# pCog105_LogicStart.net
KiCad netlist of a schematic drawn in EAGLE
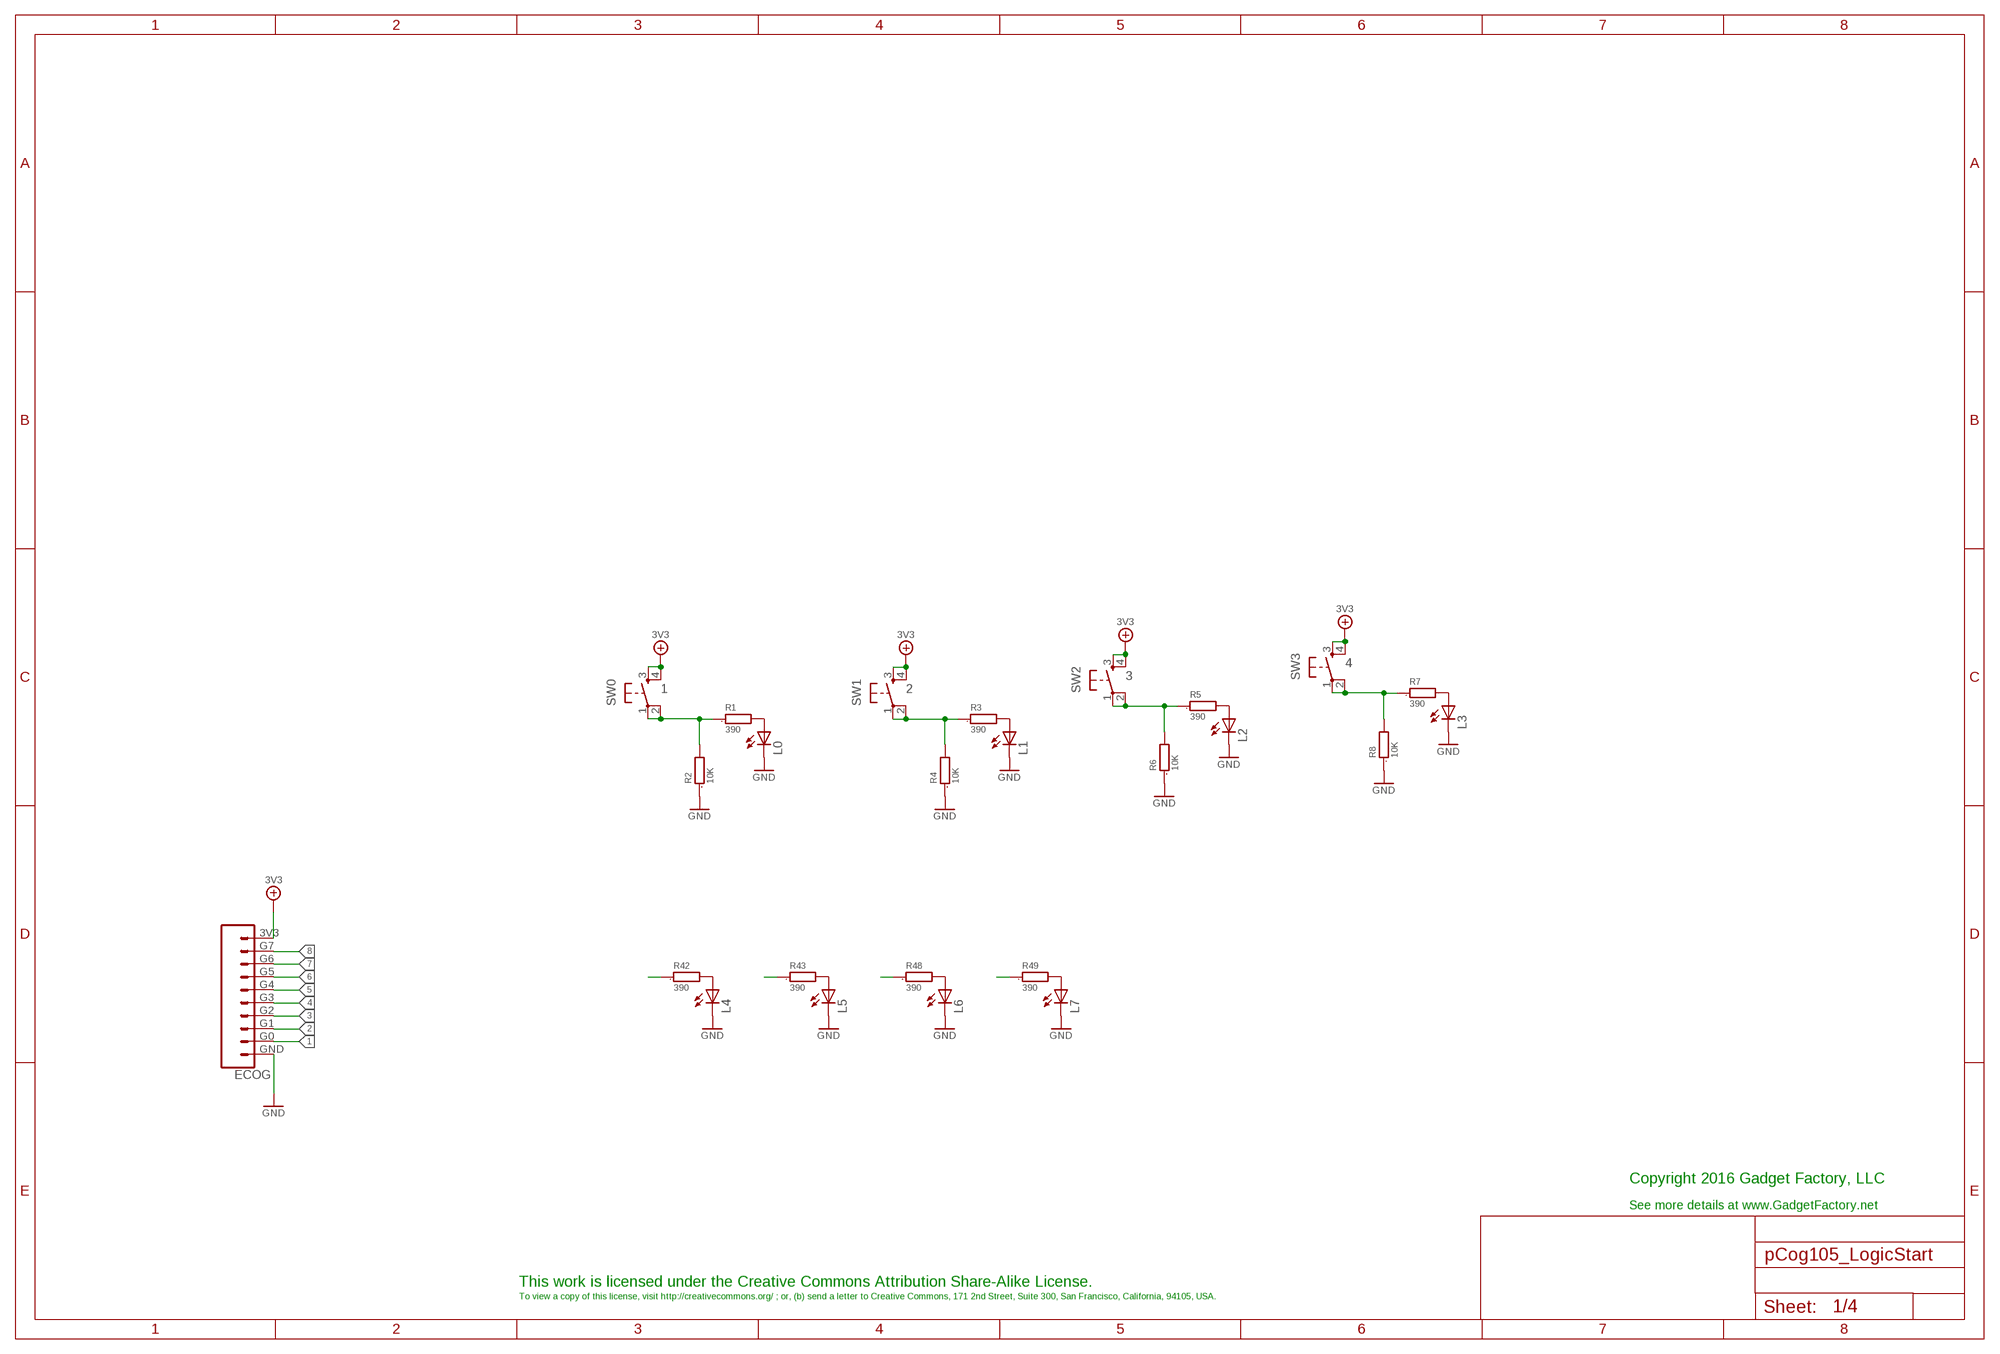
[diagram p0: schematic, sheet 1]
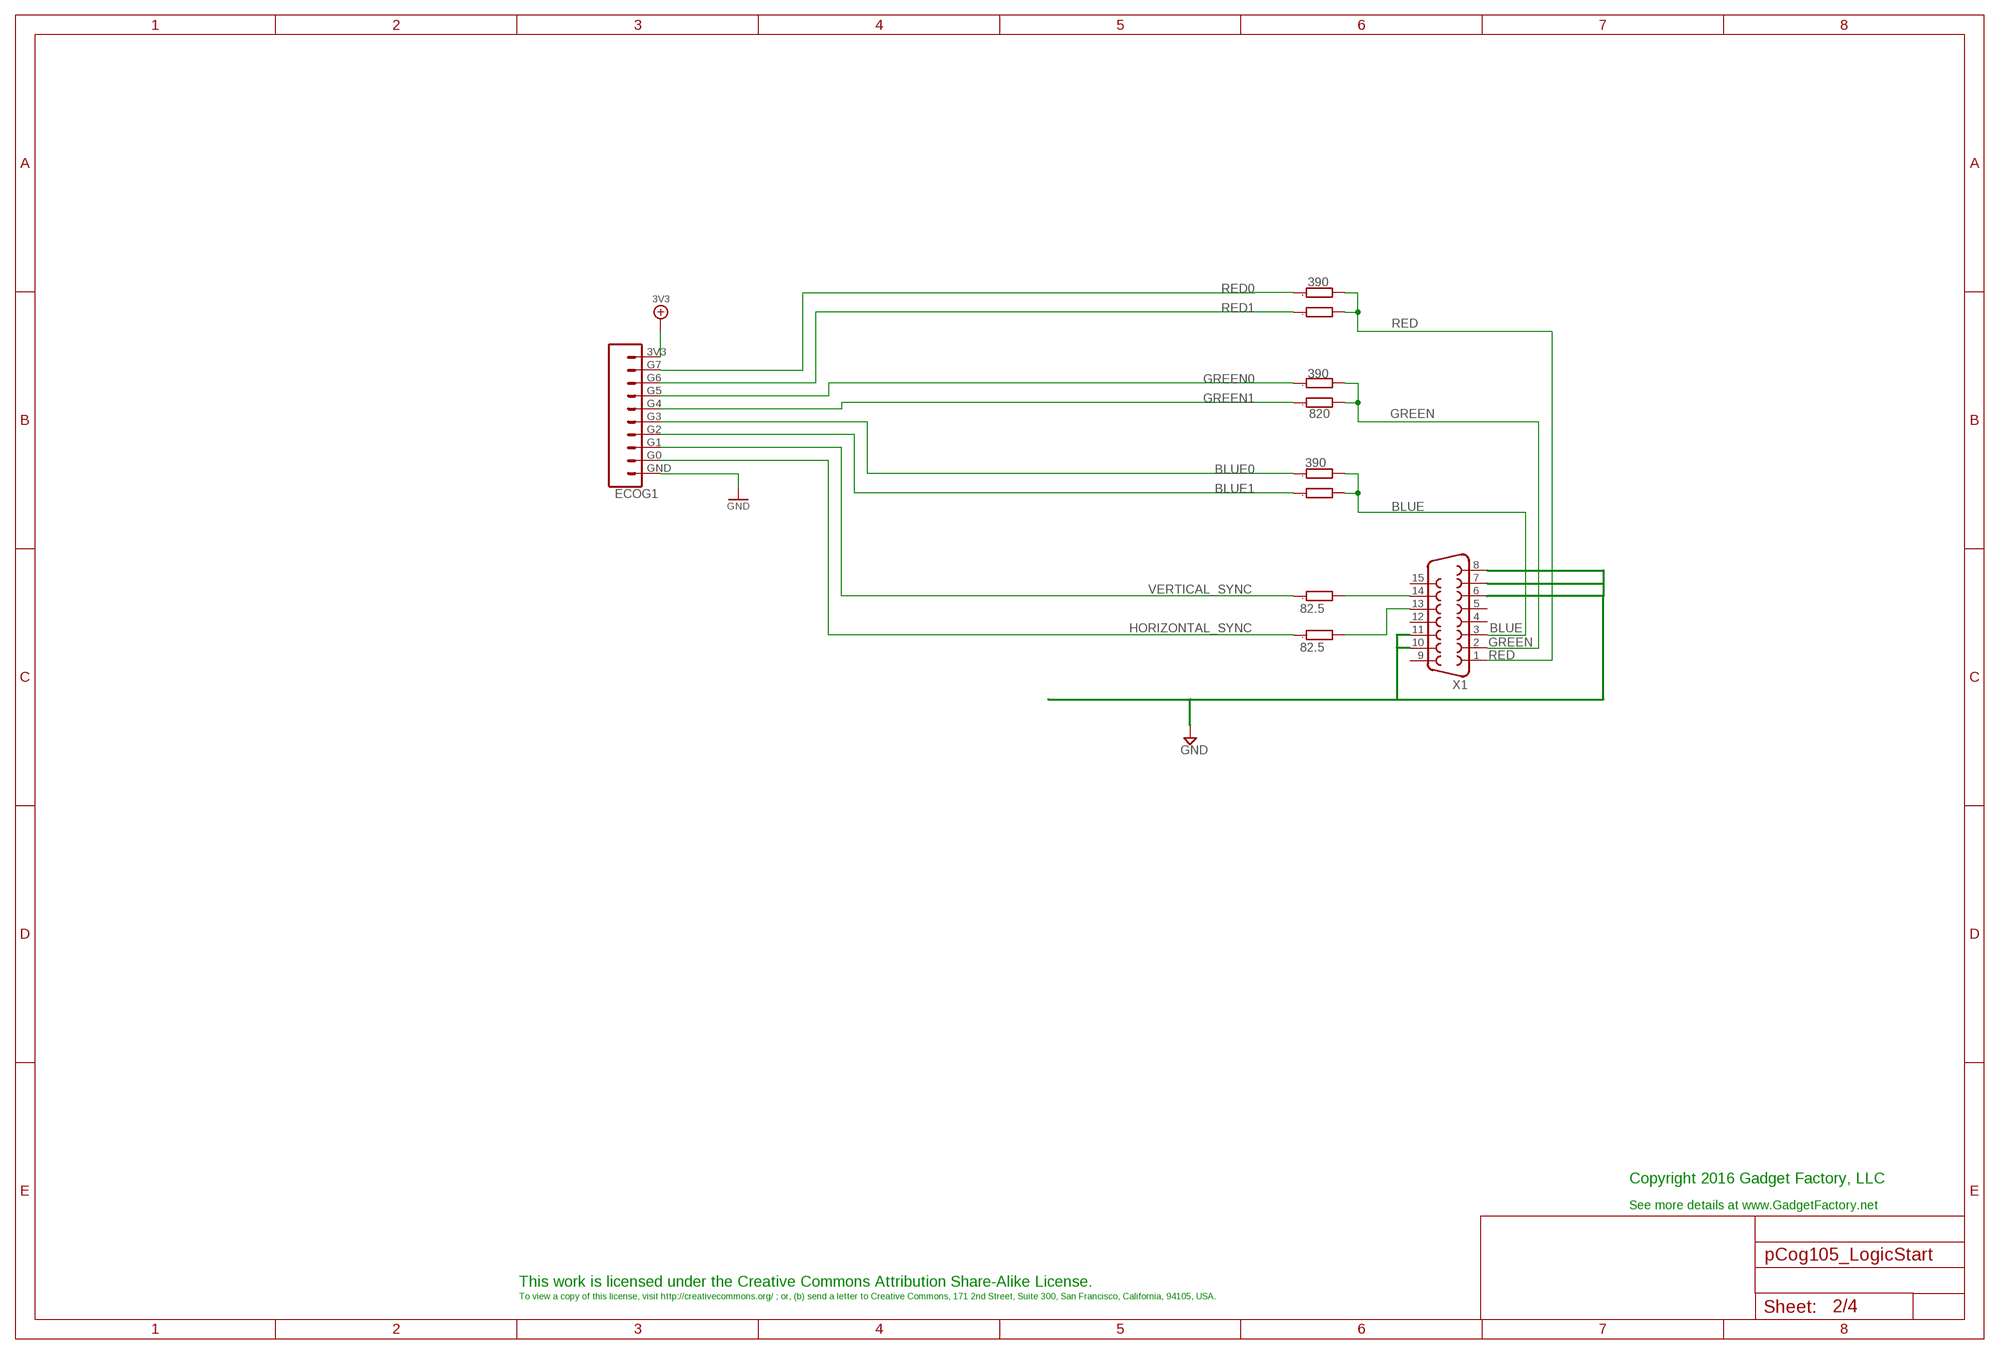
[diagram p1: schematic, sheet 2]
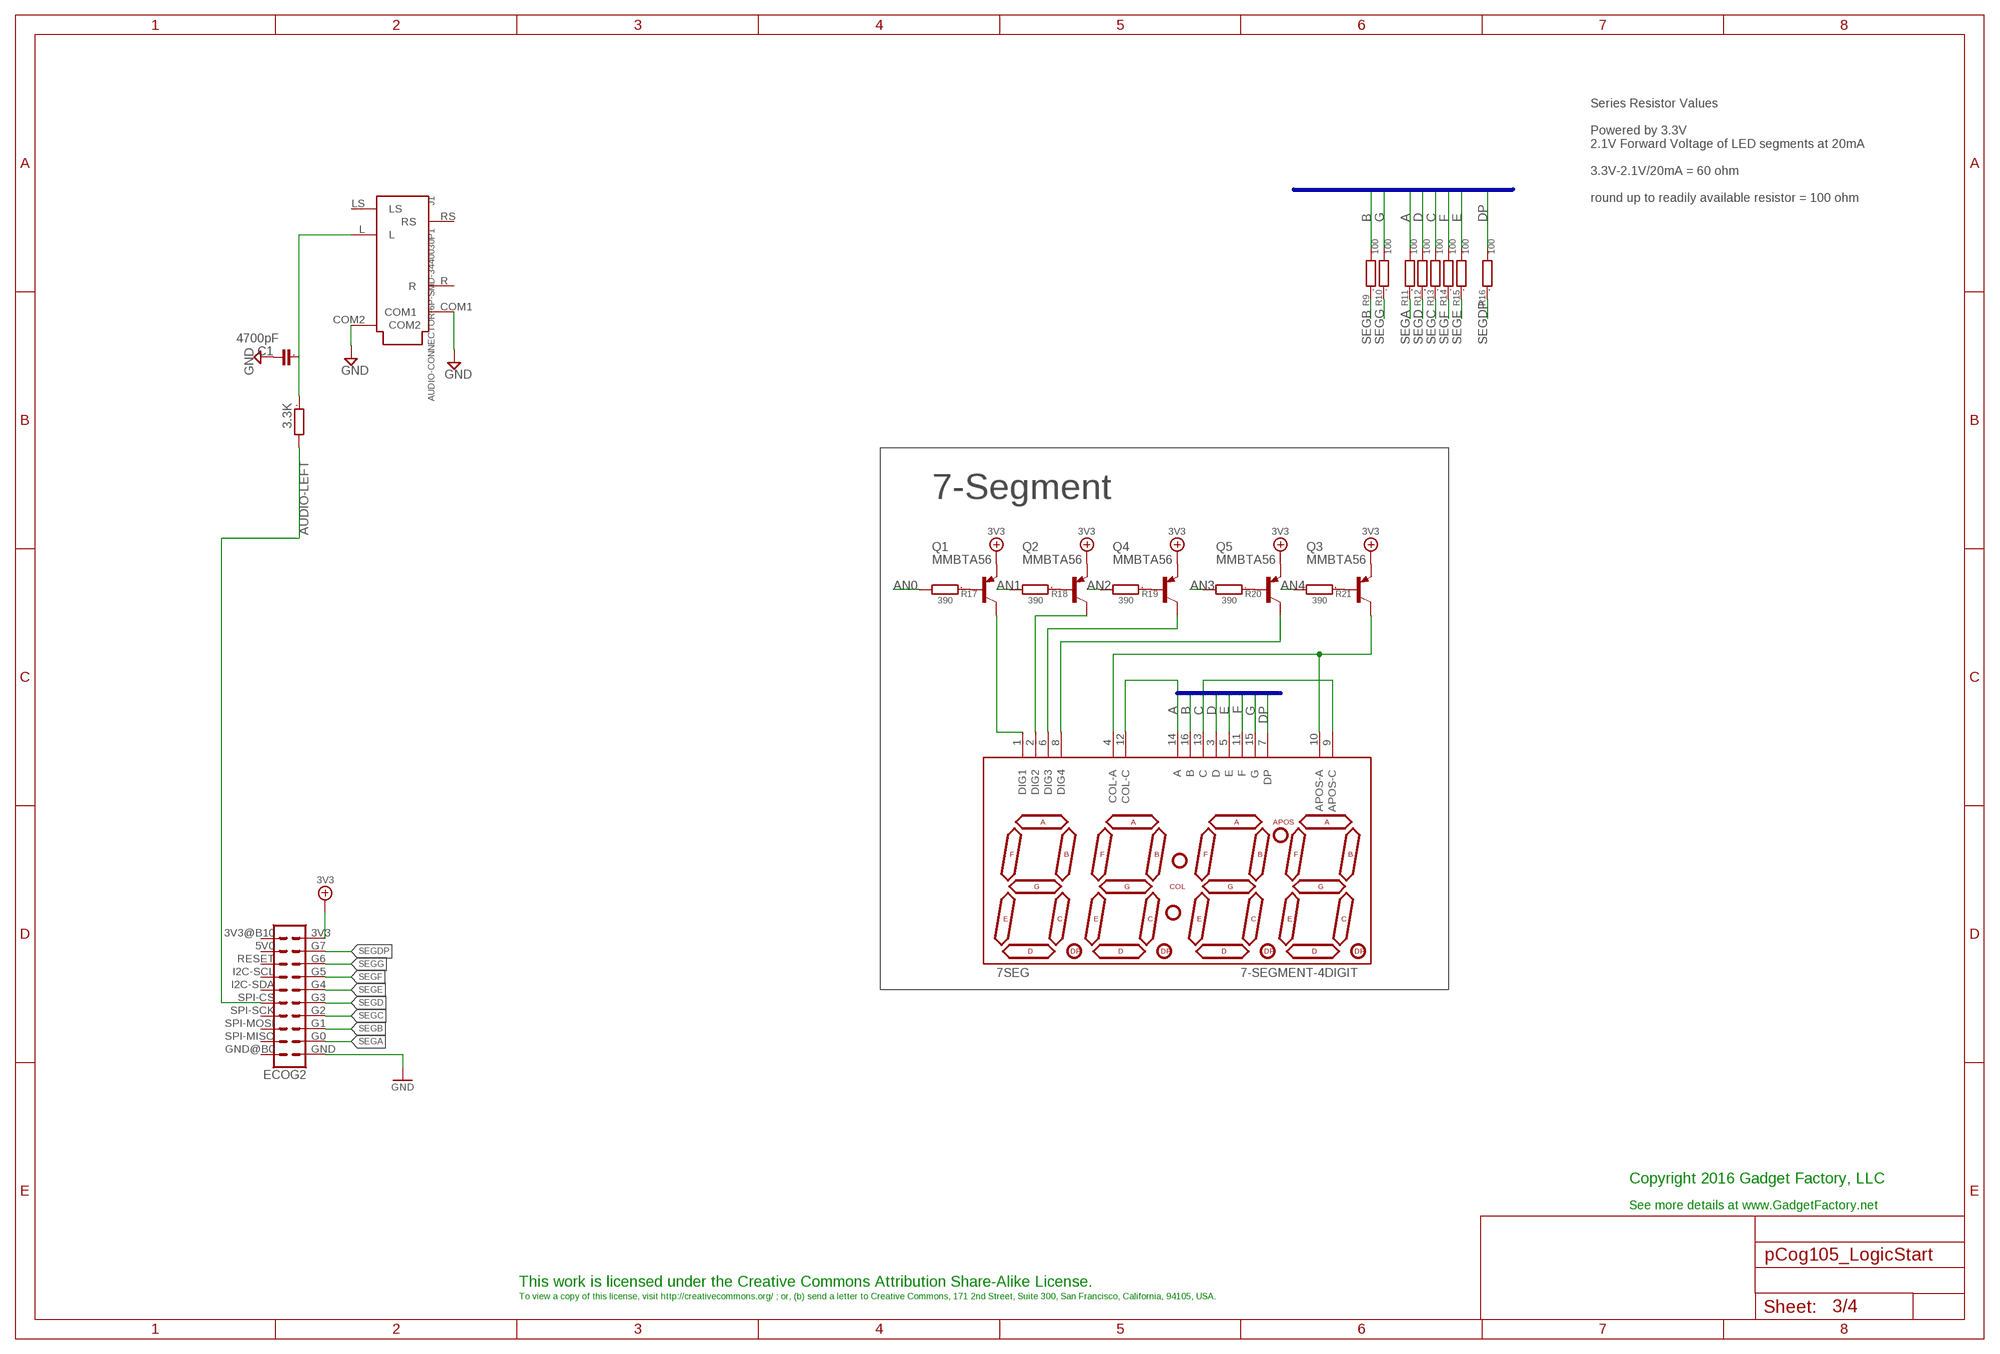
[diagram p2: schematic, sheet 3]
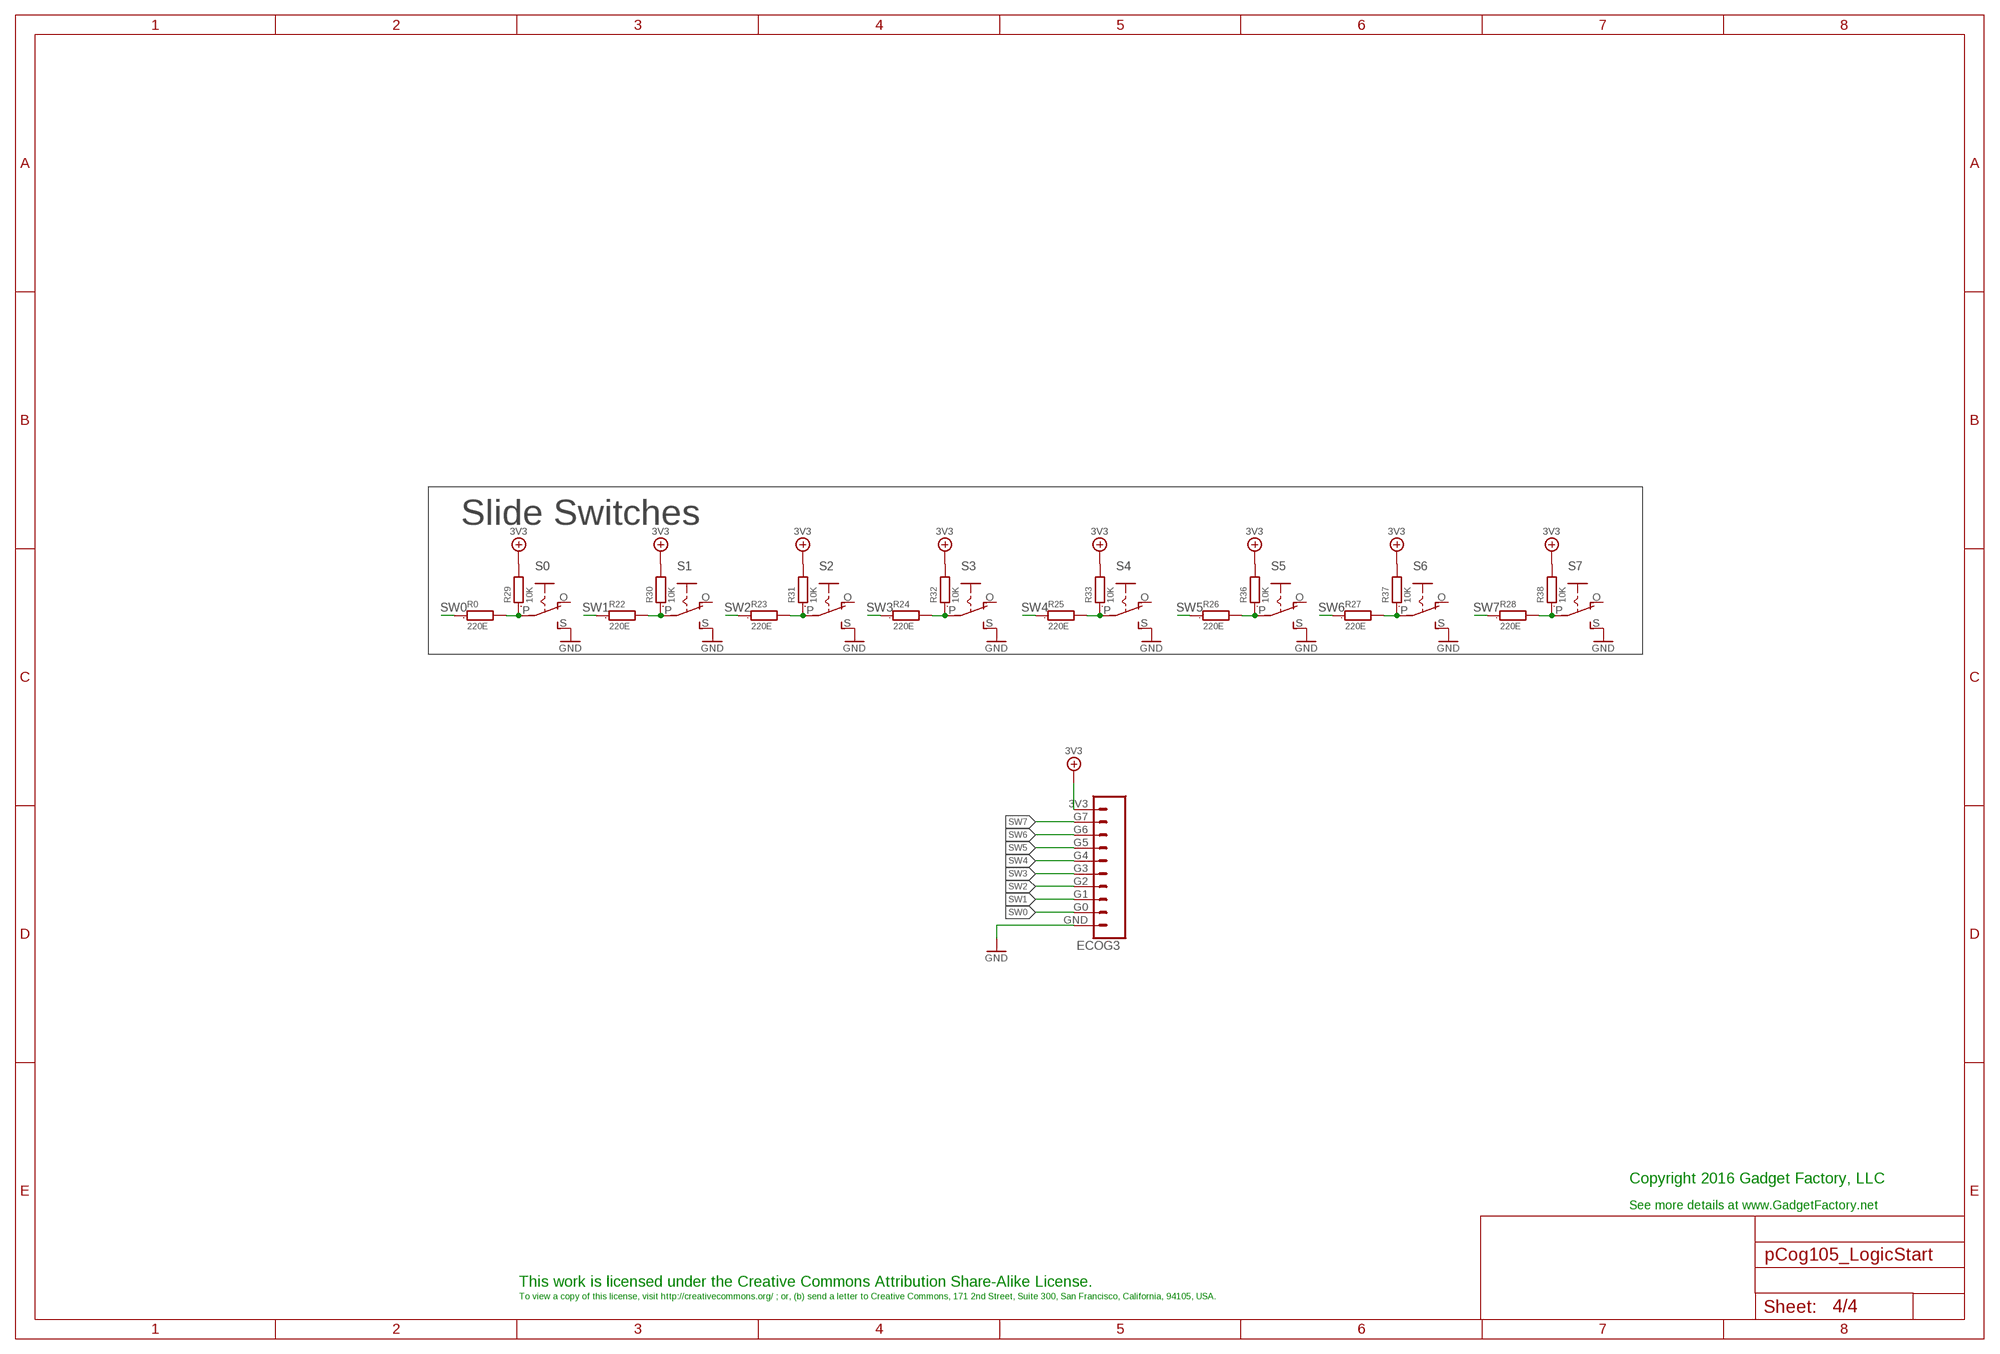
[diagram p3: schematic, sheet 4]

(export (version "E")
  (design (tool "Eeschema 10.0.6"))
  (components
    (comp (ref "ECOG")
      (value "ECOG_GENERAL_ROWTHROUGHOLE")
      (footprint "eagle-import:ECOG_GENERAL_TH")
      (libsource (lib "eagle-import") (part "ECOG_GENERAL_ROWTHROUGHOLE"))
    )
    (comp (ref "L0")
      (value "LEDCHIP-LED0805")
      (footprint "eagle-import:CHIP-LED0805")
      (libsource (lib "eagle-import") (part "LEDCHIP-LED0805"))
    )
    (comp (ref "L1")
      (value "LEDCHIP-LED0805")
      (footprint "eagle-import:CHIP-LED0805")
      (libsource (lib "eagle-import") (part "LEDCHIP-LED0805"))
    )
    (comp (ref "L2")
      (value "LEDCHIP-LED0805")
      (footprint "eagle-import:CHIP-LED0805")
      (libsource (lib "eagle-import") (part "LEDCHIP-LED0805"))
    )
    (comp (ref "L3")
      (value "LEDCHIP-LED0805")
      (footprint "eagle-import:CHIP-LED0805")
      (libsource (lib "eagle-import") (part "LEDCHIP-LED0805"))
    )
    (comp (ref "L4")
      (value "LEDCHIP-LED0805")
      (footprint "eagle-import:CHIP-LED0805")
      (libsource (lib "eagle-import") (part "LEDCHIP-LED0805"))
    )
    (comp (ref "L5")
      (value "LEDCHIP-LED0805")
      (footprint "eagle-import:CHIP-LED0805")
      (libsource (lib "eagle-import") (part "LEDCHIP-LED0805"))
    )
    (comp (ref "L6")
      (value "LEDCHIP-LED0805")
      (footprint "eagle-import:CHIP-LED0805")
      (libsource (lib "eagle-import") (part "LEDCHIP-LED0805"))
    )
    (comp (ref "L7")
      (value "LEDCHIP-LED0805")
      (footprint "eagle-import:CHIP-LED0805")
      (libsource (lib "eagle-import") (part "LEDCHIP-LED0805"))
    )
    (comp (ref "R1")
      (value "390")
      (footprint "eagle-import:0805")
      (libsource (lib "eagle-import") (part "R0805"))
    )
    (comp (ref "R2")
      (value "10K")
      (footprint "eagle-import:0805")
      (libsource (lib "eagle-import") (part "R0805"))
    )
    (comp (ref "R3")
      (value "390")
      (footprint "eagle-import:0805")
      (libsource (lib "eagle-import") (part "R0805"))
    )
    (comp (ref "R4")
      (value "10K")
      (footprint "eagle-import:0805")
      (libsource (lib "eagle-import") (part "R0805"))
    )
    (comp (ref "R5")
      (value "390")
      (footprint "eagle-import:0805")
      (libsource (lib "eagle-import") (part "R0805"))
    )
    (comp (ref "R6")
      (value "10K")
      (footprint "eagle-import:0805")
      (libsource (lib "eagle-import") (part "R0805"))
    )
    (comp (ref "R7")
      (value "390")
      (footprint "eagle-import:0805")
      (libsource (lib "eagle-import") (part "R0805"))
    )
    (comp (ref "R8")
      (value "10K")
      (footprint "eagle-import:0805")
      (libsource (lib "eagle-import") (part "R0805"))
    )
    (comp (ref "R42")
      (value "390")
      (footprint "eagle-import:0805")
      (libsource (lib "eagle-import") (part "R0805"))
    )
    (comp (ref "R43")
      (value "390")
      (footprint "eagle-import:0805")
      (libsource (lib "eagle-import") (part "R0805"))
    )
    (comp (ref "R48")
      (value "390")
      (footprint "eagle-import:0805")
      (libsource (lib "eagle-import") (part "R0805"))
    )
    (comp (ref "R49")
      (value "390")
      (footprint "eagle-import:0805")
      (libsource (lib "eagle-import") (part "R0805"))
    )
    (comp (ref "SW0")
      (value "TAC_SWITCHPTH")
      (footprint "eagle-import:TACTILE-PTH")
      (libsource (lib "eagle-import") (part "TAC_SWITCHPTH"))
    )
    (comp (ref "SW1")
      (value "TAC_SWITCHPTH")
      (footprint "eagle-import:TACTILE-PTH")
      (libsource (lib "eagle-import") (part "TAC_SWITCHPTH"))
    )
    (comp (ref "SW2")
      (value "TAC_SWITCHPTH")
      (footprint "eagle-import:TACTILE-PTH")
      (libsource (lib "eagle-import") (part "TAC_SWITCHPTH"))
    )
    (comp (ref "SW3")
      (value "TAC_SWITCHPTH")
      (footprint "eagle-import:TACTILE-PTH")
      (libsource (lib "eagle-import") (part "TAC_SWITCHPTH"))
    )
    (comp (ref "ECOG1")
      (value "ECOG_GENERAL_ROWTHROUGHOLE")
      (footprint "eagle-import:ECOG_GENERAL_TH")
      (libsource (lib "eagle-import") (part "ECOG_GENERAL_ROWTHROUGHOLE"))
    )
    (comp (ref "R34")
      (value "390")
      (footprint "eagle-import:0603")
      (fields (field (name "PARTNO") "RMCF0603JT3K90"))
      (libsource (lib "eagle-import") (part "R0603"))
    )
    (comp (ref "R35")
      (value "820")
      (footprint "eagle-import:0603")
      (fields (field (name "PARTNO") "RMCF0603JT2K00"))
      (libsource (lib "eagle-import") (part "R0603"))
    )
    (comp (ref "R40")
      (value "820")
      (footprint "eagle-import:0603")
      (fields (field (name "PARTNO") "RMCF0603JT2K00"))
      (libsource (lib "eagle-import") (part "R0603"))
    )
    (comp (ref "R41")
      (value "390")
      (footprint "eagle-import:0603")
      (fields (field (name "PARTNO") "RMCF0603JT3K90"))
      (libsource (lib "eagle-import") (part "R0603"))
    )
    (comp (ref "R44")
      (value "820")
      (footprint "eagle-import:0603")
      (fields (field (name "PARTNO") "RMCF0603JT2K00"))
      (libsource (lib "eagle-import") (part "R0603"))
    )
    (comp (ref "R45")
      (value "390")
      (footprint "eagle-import:0603")
      (fields (field (name "PARTNO") "RMCF0603JT3K90"))
      (libsource (lib "eagle-import") (part "R0603"))
    )
    (comp (ref "R46")
      (value "82.5")
      (footprint "eagle-import:0603")
      (fields (field (name "PARTNO") "RMCF0603FT82R5"))
      (libsource (lib "eagle-import") (part "R0603"))
    )
    (comp (ref "R47")
      (value "82.5")
      (footprint "eagle-import:0603")
      (fields (field (name "PARTNO") "RMCF0603FT82R5"))
      (libsource (lib "eagle-import") (part "R0603"))
    )
    (comp (ref "X1")
      (value "F15HDH")
      (footprint "eagle-import:HDF15H")
      (fields (field (name "PARTNO") "1-1734530-1"))
      (libsource (lib "eagle-import") (part "F15HDH"))
    )
    (comp (ref "ECOG3")
      (value "ECOG_GENERAL_ROWTHROUGHOLE")
      (footprint "eagle-import:ECOG_GENERAL_TH")
      (libsource (lib "eagle-import") (part "ECOG_GENERAL_ROWTHROUGHOLE"))
    )
    (comp (ref "R0")
      (value "220E")
      (footprint "eagle-import:0603")
      (fields (field (name "PARTNO") "RMCF0603JT220R"))
      (libsource (lib "eagle-import") (part "R0603"))
    )
    (comp (ref "R22")
      (value "220E")
      (footprint "eagle-import:0603")
      (fields (field (name "PARTNO") "RMCF0603JT220R"))
      (libsource (lib "eagle-import") (part "R0603"))
    )
    (comp (ref "R23")
      (value "220E")
      (footprint "eagle-import:0603")
      (fields (field (name "PARTNO") "RMCF0603JT220R"))
      (libsource (lib "eagle-import") (part "R0603"))
    )
    (comp (ref "R24")
      (value "220E")
      (footprint "eagle-import:0603")
      (fields (field (name "PARTNO") "RMCF0603JT220R"))
      (libsource (lib "eagle-import") (part "R0603"))
    )
    (comp (ref "R25")
      (value "220E")
      (footprint "eagle-import:0603")
      (fields (field (name "PARTNO") "RMCF0603JT220R"))
      (libsource (lib "eagle-import") (part "R0603"))
    )
    (comp (ref "R26")
      (value "220E")
      (footprint "eagle-import:0603")
      (fields (field (name "PARTNO") "RMCF0603JT220R"))
      (libsource (lib "eagle-import") (part "R0603"))
    )
    (comp (ref "R27")
      (value "220E")
      (footprint "eagle-import:0603")
      (fields (field (name "PARTNO") "RMCF0603JT220R"))
      (libsource (lib "eagle-import") (part "R0603"))
    )
    (comp (ref "R28")
      (value "220E")
      (footprint "eagle-import:0603")
      (fields (field (name "PARTNO") "RMCF0603JT220R"))
      (libsource (lib "eagle-import") (part "R0603"))
    )
    (comp (ref "R29")
      (value "10K")
      (footprint "eagle-import:0603")
      (fields (field (name "PARTNO") "RMCF0603JT10K0"))
      (libsource (lib "eagle-import") (part "R0603"))
    )
    (comp (ref "R30")
      (value "10K")
      (footprint "eagle-import:0603")
      (fields (field (name "PARTNO") "RMCF0603JT10K0"))
      (libsource (lib "eagle-import") (part "R0603"))
    )
    (comp (ref "R31")
      (value "10K")
      (footprint "eagle-import:0603")
      (fields (field (name "PARTNO") "RMCF0603JT10K0"))
      (libsource (lib "eagle-import") (part "R0603"))
    )
    (comp (ref "R32")
      (value "10K")
      (footprint "eagle-import:0603")
      (fields (field (name "PARTNO") "RMCF0603JT10K0"))
      (libsource (lib "eagle-import") (part "R0603"))
    )
    (comp (ref "R33")
      (value "10K")
      (footprint "eagle-import:0603")
      (fields (field (name "PARTNO") "RMCF0603JT10K0"))
      (libsource (lib "eagle-import") (part "R0603"))
    )
    (comp (ref "R36")
      (value "10K")
      (footprint "eagle-import:0603")
      (fields (field (name "PARTNO") "RMCF0603JT10K0"))
      (libsource (lib "eagle-import") (part "R0603"))
    )
    (comp (ref "R37")
      (value "10K")
      (footprint "eagle-import:0603")
      (fields (field (name "PARTNO") "RMCF0603JT10K0"))
      (libsource (lib "eagle-import") (part "R0603"))
    )
    (comp (ref "R38")
      (value "10K")
      (footprint "eagle-import:0603")
      (fields (field (name "PARTNO") "RMCF0603JT10K0"))
      (libsource (lib "eagle-import") (part "R0603"))
    )
    (comp (ref "S0")
      (value "EG1218S")
      (footprint "eagle-import:EG1218")
      (fields (field (name "PARTNO") "EG1218"))
      (libsource (lib "eagle-import") (part "EG1218S"))
    )
    (comp (ref "S1")
      (value "EG1218S")
      (footprint "eagle-import:EG1218")
      (fields (field (name "PARTNO") "EG1218"))
      (libsource (lib "eagle-import") (part "EG1218S"))
    )
    (comp (ref "S2")
      (value "EG1218S")
      (footprint "eagle-import:EG1218")
      (fields (field (name "PARTNO") "EG1218"))
      (libsource (lib "eagle-import") (part "EG1218S"))
    )
    (comp (ref "S3")
      (value "EG1218S")
      (footprint "eagle-import:EG1218")
      (fields (field (name "PARTNO") "EG1218"))
      (libsource (lib "eagle-import") (part "EG1218S"))
    )
    (comp (ref "S4")
      (value "EG1218S")
      (footprint "eagle-import:EG1218")
      (fields (field (name "PARTNO") "EG1218"))
      (libsource (lib "eagle-import") (part "EG1218S"))
    )
    (comp (ref "S5")
      (value "EG1218S")
      (footprint "eagle-import:EG1218")
      (fields (field (name "PARTNO") "EG1218"))
      (libsource (lib "eagle-import") (part "EG1218S"))
    )
    (comp (ref "S6")
      (value "EG1218S")
      (footprint "eagle-import:EG1218")
      (fields (field (name "PARTNO") "EG1218"))
      (libsource (lib "eagle-import") (part "EG1218S"))
    )
    (comp (ref "S7")
      (value "EG1218S")
      (footprint "eagle-import:EG1218")
      (fields (field (name "PARTNO") "EG1218"))
      (libsource (lib "eagle-import") (part "EG1218S"))
    )
    (comp (ref "7SEG")
      (value "7-SEGMENT-4DIGIT")
      (footprint "eagle-import:7-SEGMENT-4DIGIT")
      (fields (field (name "PARTNO") "AL-D4012BWSR/58-040C"))
      (libsource (lib "eagle-import") (part "7-SEGMENT-4DIGIT"))
    )
    (comp (ref "C1")
      (value "4700pF")
      (footprint "eagle-import:0603")
      (fields (field (name "PARTNO") "C0603C472J5RACTU"))
      (libsource (lib "eagle-import") (part "C0603"))
    )
    (comp (ref "ECOG2")
      (value "ECOG_DUALTHROUGHHOLE")
      (footprint "eagle-import:ECOG_DUAL_TH")
      (libsource (lib "eagle-import") (part "ECOG_DUALTHROUGHHOLE"))
    )
    (comp (ref "J1")
      (value "AUDIO-CONNECTOR-6P-SMD-3440030P1")
      (footprint "eagle-import:6P-SMD-3.5")
      (fields (field (name "PARTNO") "3440030P1"))
      (libsource (lib "eagle-import") (part "AUDIO-CONNECTOR-6P-SMD-3440030P1"))
    )
    (comp (ref "Q1")
      (value "MMBTA56")
      (footprint "eagle-import:SOT23")
      (libsource (lib "eagle-import") (part "-?SOT23MMBTA56"))
    )
    (comp (ref "Q2")
      (value "MMBTA56")
      (footprint "eagle-import:SOT23")
      (libsource (lib "eagle-import") (part "-?SOT23MMBTA56"))
    )
    (comp (ref "Q3")
      (value "MMBTA56")
      (footprint "eagle-import:SOT23")
      (libsource (lib "eagle-import") (part "-?SOT23MMBTA56"))
    )
    (comp (ref "Q4")
      (value "MMBTA56")
      (footprint "eagle-import:SOT23")
      (libsource (lib "eagle-import") (part "-?SOT23MMBTA56"))
    )
    (comp (ref "Q5")
      (value "MMBTA56")
      (footprint "eagle-import:SOT23")
      (libsource (lib "eagle-import") (part "-?SOT23MMBTA56"))
    )
    (comp (ref "R9")
      (value "100")
      (footprint "eagle-import:0603")
      (fields (field (name "PARTNO") "CRCW0603100RJNEA"))
      (libsource (lib "eagle-import") (part "R0603"))
    )
    (comp (ref "R10")
      (value "100")
      (footprint "eagle-import:0603")
      (fields (field (name "PARTNO") "CRCW0603100RJNEA"))
      (libsource (lib "eagle-import") (part "R0603"))
    )
    (comp (ref "R11")
      (value "100")
      (footprint "eagle-import:0603")
      (fields (field (name "PARTNO") "CRCW0603100RJNEA"))
      (libsource (lib "eagle-import") (part "R0603"))
    )
    (comp (ref "R12")
      (value "100")
      (footprint "eagle-import:0603")
      (fields (field (name "PARTNO") "CRCW0603100RJNEA"))
      (libsource (lib "eagle-import") (part "R0603"))
    )
    (comp (ref "R13")
      (value "100")
      (footprint "eagle-import:0603")
      (fields (field (name "PARTNO") "CRCW0603100RJNEA"))
      (libsource (lib "eagle-import") (part "R0603"))
    )
    (comp (ref "R14")
      (value "100")
      (footprint "eagle-import:0603")
      (fields (field (name "PARTNO") "CRCW0603100RJNEA"))
      (libsource (lib "eagle-import") (part "R0603"))
    )
    (comp (ref "R15")
      (value "100")
      (footprint "eagle-import:0603")
      (fields (field (name "PARTNO") "CRCW0603100RJNEA"))
      (libsource (lib "eagle-import") (part "R0603"))
    )
    (comp (ref "R16")
      (value "100")
      (footprint "eagle-import:0603")
      (fields (field (name "PARTNO") "CRCW0603100RJNEA"))
      (libsource (lib "eagle-import") (part "R0603"))
    )
    (comp (ref "R17")
      (value "390")
      (footprint "eagle-import:0603")
      (fields (field (name "PARTNO") "CRCW0603100RJNEA"))
      (libsource (lib "eagle-import") (part "R0603"))
    )
    (comp (ref "R18")
      (value "390")
      (footprint "eagle-import:0603")
      (fields (field (name "PARTNO") "CRCW0603100RJNEA"))
      (libsource (lib "eagle-import") (part "R0603"))
    )
    (comp (ref "R19")
      (value "390")
      (footprint "eagle-import:0603")
      (fields (field (name "PARTNO") "CRCW0603100RJNEA"))
      (libsource (lib "eagle-import") (part "R0603"))
    )
    (comp (ref "R20")
      (value "390")
      (footprint "eagle-import:0603")
      (fields (field (name "PARTNO") "CRCW0603100RJNEA"))
      (libsource (lib "eagle-import") (part "R0603"))
    )
    (comp (ref "R21")
      (value "390")
      (footprint "eagle-import:0603")
      (fields (field (name "PARTNO") "CRCW0603100RJNEA"))
      (libsource (lib "eagle-import") (part "R0603"))
    )
    (comp (ref "R39")
      (value "3.3K")
      (footprint "eagle-import:0603")
      (fields (field (name "PARTNO") "RMCF0603JT3K30"))
      (libsource (lib "eagle-import") (part "R0603"))
    )
  )
  (nets
    (net (code "1") (name "1") (class "Default")
      (node (ref "ECOG") (pin "G0") (pinfunction "G0_G0") (pintype "passive"))
      (node (ref "R1") (pin "1") (pinfunction "1_1") (pintype "passive"))
      (node (ref "R2") (pin "2") (pinfunction "2_2") (pintype "passive"))
      (node (ref "SW0") (pin "1") (pinfunction "1_1") (pintype "passive"))
      (node (ref "SW0") (pin "2") (pinfunction "2_2") (pintype "passive"))
    )
    (net (code "2") (name "2") (class "Default")
      (node (ref "ECOG") (pin "G1") (pinfunction "G1_G1") (pintype "passive"))
      (node (ref "R3") (pin "1") (pinfunction "1_1") (pintype "passive"))
      (node (ref "R4") (pin "2") (pinfunction "2_2") (pintype "passive"))
      (node (ref "SW1") (pin "1") (pinfunction "1_1") (pintype "passive"))
      (node (ref "SW1") (pin "2") (pinfunction "2_2") (pintype "passive"))
    )
    (net (code "3") (name "3") (class "Default")
      (node (ref "ECOG") (pin "G2") (pinfunction "G2_G2") (pintype "passive"))
      (node (ref "R5") (pin "1") (pinfunction "1_1") (pintype "passive"))
      (node (ref "R6") (pin "2") (pinfunction "2_2") (pintype "passive"))
      (node (ref "SW2") (pin "1") (pinfunction "1_1") (pintype "passive"))
      (node (ref "SW2") (pin "2") (pinfunction "2_2") (pintype "passive"))
    )
    (net (code "4") (name "3V3") (class "Default")
      (node (ref "ECOG") (pin "3V3") (pinfunction "3V3_3V3") (pintype "power_in"))
      (node (ref "ECOG1") (pin "3V3") (pinfunction "3V3_3V3") (pintype "power_in"))
      (node (ref "ECOG2") (pin "3V3") (pinfunction "3V3_3V3") (pintype "passive"))
      (node (ref "ECOG3") (pin "3V3") (pinfunction "3V3_3V3") (pintype "power_in"))
      (node (ref "Q1") (pin "2") (pinfunction "E_2") (pintype "passive"))
      (node (ref "Q2") (pin "2") (pinfunction "E_2") (pintype "passive"))
      (node (ref "Q3") (pin "2") (pinfunction "E_2") (pintype "passive"))
      (node (ref "Q4") (pin "2") (pinfunction "E_2") (pintype "passive"))
      (node (ref "Q5") (pin "2") (pinfunction "E_2") (pintype "passive"))
      (node (ref "R29") (pin "2") (pinfunction "2_2") (pintype "passive"))
      (node (ref "R30") (pin "2") (pinfunction "2_2") (pintype "passive"))
      (node (ref "R31") (pin "2") (pinfunction "2_2") (pintype "passive"))
      (node (ref "R32") (pin "2") (pinfunction "2_2") (pintype "passive"))
      (node (ref "R33") (pin "2") (pinfunction "2_2") (pintype "passive"))
      (node (ref "R36") (pin "2") (pinfunction "2_2") (pintype "passive"))
      (node (ref "R37") (pin "2") (pinfunction "2_2") (pintype "passive"))
      (node (ref "R38") (pin "2") (pinfunction "2_2") (pintype "passive"))
      (node (ref "SW0") (pin "3") (pinfunction "3_3") (pintype "passive"))
      (node (ref "SW0") (pin "4") (pinfunction "4_4") (pintype "passive"))
      (node (ref "SW1") (pin "3") (pinfunction "3_3") (pintype "passive"))
      (node (ref "SW1") (pin "4") (pinfunction "4_4") (pintype "passive"))
      (node (ref "SW2") (pin "3") (pinfunction "3_3") (pintype "passive"))
      (node (ref "SW2") (pin "4") (pinfunction "4_4") (pintype "passive"))
      (node (ref "SW3") (pin "3") (pinfunction "3_3") (pintype "passive"))
      (node (ref "SW3") (pin "4") (pinfunction "4_4") (pintype "passive"))
    )
    (net (code "5") (name "4") (class "Default")
      (node (ref "ECOG") (pin "G3") (pinfunction "G3_G3") (pintype "passive"))
      (node (ref "R7") (pin "1") (pinfunction "1_1") (pintype "passive"))
      (node (ref "R8") (pin "2") (pinfunction "2_2") (pintype "passive"))
      (node (ref "SW3") (pin "1") (pinfunction "1_1") (pintype "passive"))
      (node (ref "SW3") (pin "2") (pinfunction "2_2") (pintype "passive"))
    )
    (net (code "6") (name "5") (class "Default")
      (node (ref "ECOG") (pin "G4") (pinfunction "G4_G4") (pintype "passive"))
      (node (ref "R42") (pin "1") (pinfunction "1_1") (pintype "passive"))
    )
    (net (code "7") (name "6") (class "Default")
      (node (ref "ECOG") (pin "G5") (pinfunction "G5_G5") (pintype "passive"))
      (node (ref "R43") (pin "1") (pinfunction "1_1") (pintype "passive"))
    )
    (net (code "8") (name "7") (class "Default")
      (node (ref "ECOG") (pin "G6") (pinfunction "G6_G6") (pintype "passive"))
      (node (ref "R48") (pin "1") (pinfunction "1_1") (pintype "passive"))
    )
    (net (code "9") (name "8") (class "Default")
      (node (ref "ECOG") (pin "G7") (pinfunction "G7_G7") (pintype "passive"))
      (node (ref "R49") (pin "1") (pinfunction "1_1") (pintype "passive"))
    )
    (net (code "10") (name "A") (class "Default")
      (node (ref "7SEG") (pin "12") (pinfunction "COL-C_12") (pintype "bidirectional"))
      (node (ref "7SEG") (pin "14") (pinfunction "A_14") (pintype "bidirectional"))
      (node (ref "R11") (pin "2") (pinfunction "2_2") (pintype "passive"))
    )
    (net (code "11") (name "AN0") (class "Default")
      (node (ref "R17") (pin "2") (pinfunction "2_2") (pintype "passive"))
    )
    (net (code "12") (name "AN1") (class "Default")
      (node (ref "R18") (pin "2") (pinfunction "2_2") (pintype "passive"))
    )
    (net (code "13") (name "AN2") (class "Default")
      (node (ref "R19") (pin "2") (pinfunction "2_2") (pintype "passive"))
    )
    (net (code "14") (name "AN3") (class "Default")
      (node (ref "R20") (pin "2") (pinfunction "2_2") (pintype "passive"))
    )
    (net (code "15") (name "AN4") (class "Default")
      (node (ref "R21") (pin "2") (pinfunction "2_2") (pintype "passive"))
    )
    (net (code "16") (name "AUDIO-LEFT") (class "Default")
      (node (ref "ECOG2") (pin "SPI-CS") (pinfunction "SPI-CS_SPI-CS") (pintype "passive"))
      (node (ref "R39") (pin "2") (pinfunction "2_2") (pintype "passive"))
    )
    (net (code "17") (name "B") (class "Default")
      (node (ref "7SEG") (pin "16") (pinfunction "B_16") (pintype "bidirectional"))
      (node (ref "R9") (pin "2") (pinfunction "2_2") (pintype "passive"))
    )
    (net (code "18") (name "BLUE") (class "Default")
      (node (ref "R44") (pin "2") (pinfunction "2_2") (pintype "passive"))
      (node (ref "R45") (pin "2") (pinfunction "2_2") (pintype "passive"))
      (node (ref "X1") (pin "3") (pinfunction "3_3") (pintype "passive"))
    )
    (net (code "19") (name "BLUE0") (class "Default")
      (node (ref "ECOG1") (pin "G3") (pinfunction "G3_G3") (pintype "passive"))
      (node (ref "R45") (pin "1") (pinfunction "1_1") (pintype "passive"))
    )
    (net (code "20") (name "BLUE1") (class "Default")
      (node (ref "ECOG1") (pin "G2") (pinfunction "G2_G2") (pintype "passive"))
      (node (ref "R44") (pin "1") (pinfunction "1_1") (pintype "passive"))
    )
    (net (code "21") (name "C") (class "Default")
      (node (ref "7SEG") (pin "13") (pinfunction "C_13") (pintype "bidirectional"))
      (node (ref "7SEG") (pin "9") (pinfunction "APOS-C_9") (pintype "bidirectional"))
      (node (ref "R13") (pin "2") (pinfunction "2_2") (pintype "passive"))
    )
    (net (code "22") (name "D") (class "Default")
      (node (ref "7SEG") (pin "3") (pinfunction "D_3") (pintype "bidirectional"))
      (node (ref "R12") (pin "2") (pinfunction "2_2") (pintype "passive"))
    )
    (net (code "23") (name "DP") (class "Default")
      (node (ref "7SEG") (pin "7") (pinfunction "DP_7") (pintype "bidirectional"))
      (node (ref "R16") (pin "2") (pinfunction "2_2") (pintype "passive"))
    )
    (net (code "24") (name "E") (class "Default")
      (node (ref "7SEG") (pin "5") (pinfunction "E_5") (pintype "bidirectional"))
      (node (ref "R15") (pin "2") (pinfunction "2_2") (pintype "passive"))
    )
    (net (code "25") (name "F") (class "Default")
      (node (ref "7SEG") (pin "11") (pinfunction "F_11") (pintype "bidirectional"))
      (node (ref "R14") (pin "2") (pinfunction "2_2") (pintype "passive"))
    )
    (net (code "26") (name "G") (class "Default")
      (node (ref "7SEG") (pin "15") (pinfunction "G_15") (pintype "bidirectional"))
      (node (ref "R10") (pin "2") (pinfunction "2_2") (pintype "passive"))
    )
    (net (code "27") (name "GND") (class "Default")
      (node (ref "C1") (pin "2") (pinfunction "2_2") (pintype "passive"))
      (node (ref "ECOG") (pin "GND") (pinfunction "GND_GND") (pintype "power_in"))
      (node (ref "ECOG1") (pin "GND") (pinfunction "GND_GND") (pintype "power_in"))
      (node (ref "ECOG2") (pin "GND") (pinfunction "GND_GND") (pintype "passive"))
      (node (ref "ECOG3") (pin "GND") (pinfunction "GND_GND") (pintype "power_in"))
      (node (ref "J1") (pin "COM1") (pinfunction "COM1_COM1") (pintype "bidirectional"))
      (node (ref "J1") (pin "COM2") (pinfunction "COM2_COM2") (pintype "bidirectional"))
      (node (ref "L0") (pin "C") (pinfunction "C_C") (pintype "passive"))
      (node (ref "L1") (pin "C") (pinfunction "C_C") (pintype "passive"))
      (node (ref "L2") (pin "C") (pinfunction "C_C") (pintype "passive"))
      (node (ref "L3") (pin "C") (pinfunction "C_C") (pintype "passive"))
      (node (ref "L4") (pin "C") (pinfunction "C_C") (pintype "passive"))
      (node (ref "L5") (pin "C") (pinfunction "C_C") (pintype "passive"))
      (node (ref "L6") (pin "C") (pinfunction "C_C") (pintype "passive"))
      (node (ref "L7") (pin "C") (pinfunction "C_C") (pintype "passive"))
      (node (ref "R2") (pin "1") (pinfunction "1_1") (pintype "passive"))
      (node (ref "R4") (pin "1") (pinfunction "1_1") (pintype "passive"))
      (node (ref "R6") (pin "1") (pinfunction "1_1") (pintype "passive"))
      (node (ref "R8") (pin "1") (pinfunction "1_1") (pintype "passive"))
      (node (ref "S0") (pin "S") (pinfunction "S_S") (pintype "passive"))
      (node (ref "S1") (pin "S") (pinfunction "S_S") (pintype "passive"))
      (node (ref "S2") (pin "S") (pinfunction "S_S") (pintype "passive"))
      (node (ref "S3") (pin "S") (pinfunction "S_S") (pintype "passive"))
      (node (ref "S4") (pin "S") (pinfunction "S_S") (pintype "passive"))
      (node (ref "S5") (pin "S") (pinfunction "S_S") (pintype "passive"))
      (node (ref "S6") (pin "S") (pinfunction "S_S") (pintype "passive"))
      (node (ref "S7") (pin "S") (pinfunction "S_S") (pintype "passive"))
      (node (ref "X1") (pin "10") (pinfunction "10_10") (pintype "passive"))
      (node (ref "X1") (pin "11") (pinfunction "11_11") (pintype "passive"))
      (node (ref "X1") (pin "6") (pinfunction "6_6") (pintype "passive"))
      (node (ref "X1") (pin "7") (pinfunction "7_7") (pintype "passive"))
      (node (ref "X1") (pin "8") (pinfunction "8_8") (pintype "passive"))
    )
    (net (code "28") (name "GREEN") (class "Default")
      (node (ref "R40") (pin "2") (pinfunction "2_2") (pintype "passive"))
      (node (ref "R41") (pin "2") (pinfunction "2_2") (pintype "passive"))
      (node (ref "X1") (pin "2") (pinfunction "2_2") (pintype "passive"))
    )
    (net (code "29") (name "GREEN0") (class "Default")
      (node (ref "ECOG1") (pin "G5") (pinfunction "G5_G5") (pintype "passive"))
      (node (ref "R41") (pin "1") (pinfunction "1_1") (pintype "passive"))
    )
    (net (code "30") (name "GREEN1") (class "Default")
      (node (ref "ECOG1") (pin "G4") (pinfunction "G4_G4") (pintype "passive"))
      (node (ref "R40") (pin "1") (pinfunction "1_1") (pintype "passive"))
    )
    (net (code "31") (name "HORIZONTAL_SYNC") (class "Default")
      (node (ref "ECOG1") (pin "G0") (pinfunction "G0_G0") (pintype "passive"))
      (node (ref "R47") (pin "1") (pinfunction "1_1") (pintype "passive"))
    )
    (net (code "32") (name "Net-(7SEG-APOS-A)") (class "Default")
      (node (ref "7SEG") (pin "10") (pinfunction "APOS-A_10") (pintype "bidirectional"))
      (node (ref "7SEG") (pin "4") (pinfunction "COL-A_4") (pintype "bidirectional"))
      (node (ref "Q3") (pin "3") (pinfunction "C_3") (pintype "passive"))
    )
    (net (code "33") (name "Net-(7SEG-DIG1)") (class "Default")
      (node (ref "7SEG") (pin "1") (pinfunction "DIG1_1") (pintype "bidirectional"))
      (node (ref "Q1") (pin "3") (pinfunction "C_3") (pintype "passive"))
    )
    (net (code "34") (name "Net-(7SEG-DIG2)") (class "Default")
      (node (ref "7SEG") (pin "2") (pinfunction "DIG2_2") (pintype "bidirectional"))
      (node (ref "Q2") (pin "3") (pinfunction "C_3") (pintype "passive"))
    )
    (net (code "35") (name "Net-(7SEG-DIG3)") (class "Default")
      (node (ref "7SEG") (pin "6") (pinfunction "DIG3_6") (pintype "bidirectional"))
      (node (ref "Q4") (pin "3") (pinfunction "C_3") (pintype "passive"))
    )
    (net (code "36") (name "Net-(7SEG-DIG4)") (class "Default")
      (node (ref "7SEG") (pin "8") (pinfunction "DIG4_8") (pintype "bidirectional"))
      (node (ref "Q5") (pin "3") (pinfunction "C_3") (pintype "passive"))
    )
    (net (code "37") (name "Net-(C1-Pad1)") (class "Default")
      (node (ref "C1") (pin "1") (pinfunction "1_1") (pintype "passive"))
      (node (ref "J1") (pin "L") (pinfunction "L_L") (pintype "bidirectional"))
      (node (ref "R39") (pin "1") (pinfunction "1_1") (pintype "passive"))
    )
    (net (code "38") (name "Net-(L0-PadA)") (class "Default")
      (node (ref "L0") (pin "A") (pinfunction "A_A") (pintype "passive"))
      (node (ref "R1") (pin "2") (pinfunction "2_2") (pintype "passive"))
    )
    (net (code "39") (name "Net-(L1-PadA)") (class "Default")
      (node (ref "L1") (pin "A") (pinfunction "A_A") (pintype "passive"))
      (node (ref "R3") (pin "2") (pinfunction "2_2") (pintype "passive"))
    )
    (net (code "40") (name "Net-(L2-PadA)") (class "Default")
      (node (ref "L2") (pin "A") (pinfunction "A_A") (pintype "passive"))
      (node (ref "R5") (pin "2") (pinfunction "2_2") (pintype "passive"))
    )
    (net (code "41") (name "Net-(L3-PadA)") (class "Default")
      (node (ref "L3") (pin "A") (pinfunction "A_A") (pintype "passive"))
      (node (ref "R7") (pin "2") (pinfunction "2_2") (pintype "passive"))
    )
    (net (code "42") (name "Net-(L4-PadA)") (class "Default")
      (node (ref "L4") (pin "A") (pinfunction "A_A") (pintype "passive"))
      (node (ref "R42") (pin "2") (pinfunction "2_2") (pintype "passive"))
    )
    (net (code "43") (name "Net-(L5-PadA)") (class "Default")
      (node (ref "L5") (pin "A") (pinfunction "A_A") (pintype "passive"))
      (node (ref "R43") (pin "2") (pinfunction "2_2") (pintype "passive"))
    )
    (net (code "44") (name "Net-(L6-PadA)") (class "Default")
      (node (ref "L6") (pin "A") (pinfunction "A_A") (pintype "passive"))
      (node (ref "R48") (pin "2") (pinfunction "2_2") (pintype "passive"))
    )
    (net (code "45") (name "Net-(L7-PadA)") (class "Default")
      (node (ref "L7") (pin "A") (pinfunction "A_A") (pintype "passive"))
      (node (ref "R49") (pin "2") (pinfunction "2_2") (pintype "passive"))
    )
    (net (code "46") (name "Net-(Q1-B)") (class "Default")
      (node (ref "Q1") (pin "1") (pinfunction "B_1") (pintype "passive"))
      (node (ref "R17") (pin "1") (pinfunction "1_1") (pintype "passive"))
    )
    (net (code "47") (name "Net-(Q2-B)") (class "Default")
      (node (ref "Q2") (pin "1") (pinfunction "B_1") (pintype "passive"))
      (node (ref "R18") (pin "1") (pinfunction "1_1") (pintype "passive"))
    )
    (net (code "48") (name "Net-(Q3-B)") (class "Default")
      (node (ref "Q3") (pin "1") (pinfunction "B_1") (pintype "passive"))
      (node (ref "R21") (pin "1") (pinfunction "1_1") (pintype "passive"))
    )
    (net (code "49") (name "Net-(Q4-B)") (class "Default")
      (node (ref "Q4") (pin "1") (pinfunction "B_1") (pintype "passive"))
      (node (ref "R19") (pin "1") (pinfunction "1_1") (pintype "passive"))
    )
    (net (code "50") (name "Net-(Q5-B)") (class "Default")
      (node (ref "Q5") (pin "1") (pinfunction "B_1") (pintype "passive"))
      (node (ref "R20") (pin "1") (pinfunction "1_1") (pintype "passive"))
    )
    (net (code "51") (name "Net-(R0-Pad2)") (class "Default")
      (node (ref "R0") (pin "2") (pinfunction "2_2") (pintype "passive"))
      (node (ref "R29") (pin "1") (pinfunction "1_1") (pintype "passive"))
      (node (ref "S0") (pin "P") (pinfunction "P_P") (pintype "passive"))
    )
    (net (code "52") (name "Net-(R22-Pad2)") (class "Default")
      (node (ref "R22") (pin "2") (pinfunction "2_2") (pintype "passive"))
      (node (ref "R30") (pin "1") (pinfunction "1_1") (pintype "passive"))
      (node (ref "S1") (pin "P") (pinfunction "P_P") (pintype "passive"))
    )
    (net (code "53") (name "Net-(R23-Pad2)") (class "Default")
      (node (ref "R23") (pin "2") (pinfunction "2_2") (pintype "passive"))
      (node (ref "R31") (pin "1") (pinfunction "1_1") (pintype "passive"))
      (node (ref "S2") (pin "P") (pinfunction "P_P") (pintype "passive"))
    )
    (net (code "54") (name "Net-(R24-Pad2)") (class "Default")
      (node (ref "R24") (pin "2") (pinfunction "2_2") (pintype "passive"))
      (node (ref "R32") (pin "1") (pinfunction "1_1") (pintype "passive"))
      (node (ref "S3") (pin "P") (pinfunction "P_P") (pintype "passive"))
    )
    (net (code "55") (name "Net-(R25-Pad2)") (class "Default")
      (node (ref "R25") (pin "2") (pinfunction "2_2") (pintype "passive"))
      (node (ref "R33") (pin "1") (pinfunction "1_1") (pintype "passive"))
      (node (ref "S4") (pin "P") (pinfunction "P_P") (pintype "passive"))
    )
    (net (code "56") (name "Net-(R26-Pad2)") (class "Default")
      (node (ref "R26") (pin "2") (pinfunction "2_2") (pintype "passive"))
      (node (ref "R36") (pin "1") (pinfunction "1_1") (pintype "passive"))
      (node (ref "S5") (pin "P") (pinfunction "P_P") (pintype "passive"))
    )
    (net (code "57") (name "Net-(R27-Pad2)") (class "Default")
      (node (ref "R27") (pin "2") (pinfunction "2_2") (pintype "passive"))
      (node (ref "R37") (pin "1") (pinfunction "1_1") (pintype "passive"))
      (node (ref "S6") (pin "P") (pinfunction "P_P") (pintype "passive"))
    )
    (net (code "58") (name "Net-(R28-Pad2)") (class "Default")
      (node (ref "R28") (pin "2") (pinfunction "2_2") (pintype "passive"))
      (node (ref "R38") (pin "1") (pinfunction "1_1") (pintype "passive"))
      (node (ref "S7") (pin "P") (pinfunction "P_P") (pintype "passive"))
    )
    (net (code "59") (name "Net-(R46-Pad2)") (class "Default")
      (node (ref "R46") (pin "2") (pinfunction "2_2") (pintype "passive"))
      (node (ref "X1") (pin "14") (pinfunction "14_14") (pintype "passive"))
    )
    (net (code "60") (name "Net-(R47-Pad2)") (class "Default")
      (node (ref "R47") (pin "2") (pinfunction "2_2") (pintype "passive"))
      (node (ref "X1") (pin "13") (pinfunction "13_13") (pintype "passive"))
    )
    (net (code "61") (name "RED") (class "Default")
      (node (ref "R34") (pin "2") (pinfunction "2_2") (pintype "passive"))
      (node (ref "R35") (pin "2") (pinfunction "2_2") (pintype "passive"))
      (node (ref "X1") (pin "1") (pinfunction "1_1") (pintype "passive"))
    )
    (net (code "62") (name "RED0") (class "Default")
      (node (ref "ECOG1") (pin "G7") (pinfunction "G7_G7") (pintype "passive"))
      (node (ref "R34") (pin "1") (pinfunction "1_1") (pintype "passive"))
    )
    (net (code "63") (name "RED1") (class "Default")
      (node (ref "ECOG1") (pin "G6") (pinfunction "G6_G6") (pintype "passive"))
      (node (ref "R35") (pin "1") (pinfunction "1_1") (pintype "passive"))
    )
    (net (code "64") (name "SEGA") (class "Default")
      (node (ref "ECOG2") (pin "G0") (pinfunction "G0_G0") (pintype "passive"))
      (node (ref "R11") (pin "1") (pinfunction "1_1") (pintype "passive"))
    )
    (net (code "65") (name "SEGB") (class "Default")
      (node (ref "ECOG2") (pin "G1") (pinfunction "G1_G1") (pintype "passive"))
      (node (ref "R9") (pin "1") (pinfunction "1_1") (pintype "passive"))
    )
    (net (code "66") (name "SEGC") (class "Default")
      (node (ref "ECOG2") (pin "G2") (pinfunction "G2_G2") (pintype "passive"))
      (node (ref "R13") (pin "1") (pinfunction "1_1") (pintype "passive"))
    )
    (net (code "67") (name "SEGD") (class "Default")
      (node (ref "ECOG2") (pin "G3") (pinfunction "G3_G3") (pintype "passive"))
      (node (ref "R12") (pin "1") (pinfunction "1_1") (pintype "passive"))
    )
    (net (code "68") (name "SEGDP") (class "Default")
      (node (ref "ECOG2") (pin "G7") (pinfunction "G7_G7") (pintype "passive"))
      (node (ref "R16") (pin "1") (pinfunction "1_1") (pintype "passive"))
    )
    (net (code "69") (name "SEGE") (class "Default")
      (node (ref "ECOG2") (pin "G4") (pinfunction "G4_G4") (pintype "passive"))
      (node (ref "R15") (pin "1") (pinfunction "1_1") (pintype "passive"))
    )
    (net (code "70") (name "SEGF") (class "Default")
      (node (ref "ECOG2") (pin "G5") (pinfunction "G5_G5") (pintype "passive"))
      (node (ref "R14") (pin "1") (pinfunction "1_1") (pintype "passive"))
    )
    (net (code "71") (name "SEGG") (class "Default")
      (node (ref "ECOG2") (pin "G6") (pinfunction "G6_G6") (pintype "passive"))
      (node (ref "R10") (pin "1") (pinfunction "1_1") (pintype "passive"))
    )
    (net (code "72") (name "SW0") (class "Default")
      (node (ref "ECOG3") (pin "G0") (pinfunction "G0_G0") (pintype "passive"))
      (node (ref "R0") (pin "1") (pinfunction "1_1") (pintype "passive"))
    )
    (net (code "73") (name "SW1") (class "Default")
      (node (ref "ECOG3") (pin "G1") (pinfunction "G1_G1") (pintype "passive"))
      (node (ref "R22") (pin "1") (pinfunction "1_1") (pintype "passive"))
    )
    (net (code "74") (name "SW2") (class "Default")
      (node (ref "ECOG3") (pin "G2") (pinfunction "G2_G2") (pintype "passive"))
      (node (ref "R23") (pin "1") (pinfunction "1_1") (pintype "passive"))
    )
    (net (code "75") (name "SW3") (class "Default")
      (node (ref "ECOG3") (pin "G3") (pinfunction "G3_G3") (pintype "passive"))
      (node (ref "R24") (pin "1") (pinfunction "1_1") (pintype "passive"))
    )
    (net (code "76") (name "SW4") (class "Default")
      (node (ref "ECOG3") (pin "G4") (pinfunction "G4_G4") (pintype "passive"))
      (node (ref "R25") (pin "1") (pinfunction "1_1") (pintype "passive"))
    )
    (net (code "77") (name "SW5") (class "Default")
      (node (ref "ECOG3") (pin "G5") (pinfunction "G5_G5") (pintype "passive"))
      (node (ref "R26") (pin "1") (pinfunction "1_1") (pintype "passive"))
    )
    (net (code "78") (name "SW6") (class "Default")
      (node (ref "ECOG3") (pin "G6") (pinfunction "G6_G6") (pintype "passive"))
      (node (ref "R27") (pin "1") (pinfunction "1_1") (pintype "passive"))
    )
    (net (code "79") (name "SW7") (class "Default")
      (node (ref "ECOG3") (pin "G7") (pinfunction "G7_G7") (pintype "passive"))
      (node (ref "R28") (pin "1") (pinfunction "1_1") (pintype "passive"))
    )
    (net (code "80") (name "VERTICAL_SYNC") (class "Default")
      (node (ref "ECOG1") (pin "G1") (pinfunction "G1_G1") (pintype "passive"))
      (node (ref "R46") (pin "1") (pinfunction "1_1") (pintype "passive"))
    )
    (net (code "81") (name "unconnected-(ECOG2-3V3-Pad3V3@B10)") (class "Default")
      (node (ref "ECOG2") (pin "3V3@B10") (pinfunction "3V3_3V3@B10") (pintype "passive"))
    )
    (net (code "82") (name "unconnected-(ECOG2-5V-Pad5V0)") (class "Default")
      (node (ref "ECOG2") (pin "5V0") (pinfunction "5V_5V0") (pintype "passive"))
    )
    (net (code "83") (name "unconnected-(ECOG2-GND-PadGND@B0)") (class "Default")
      (node (ref "ECOG2") (pin "GND@B0") (pinfunction "GND_GND@B0") (pintype "passive"))
    )
    (net (code "84") (name "unconnected-(ECOG2-PadI2C-SCL)") (class "Default")
      (node (ref "ECOG2") (pin "I2C-SCL") (pinfunction "I2C-SCL_I2C-SCL") (pintype "passive"))
    )
    (net (code "85") (name "unconnected-(ECOG2-PadI2C-SDA)") (class "Default")
      (node (ref "ECOG2") (pin "I2C-SDA") (pinfunction "I2C-SDA_I2C-SDA") (pintype "passive"))
    )
    (net (code "86") (name "unconnected-(ECOG2-PadRESET)") (class "Default")
      (node (ref "ECOG2") (pin "RESET") (pinfunction "RESET_RESET") (pintype "passive"))
    )
    (net (code "87") (name "unconnected-(ECOG2-PadSPI-MISO)") (class "Default")
      (node (ref "ECOG2") (pin "SPI-MISO") (pinfunction "SPI-MISO_SPI-MISO") (pintype "passive"))
    )
    (net (code "88") (name "unconnected-(ECOG2-PadSPI-MOSI)") (class "Default")
      (node (ref "ECOG2") (pin "SPI-MOSI") (pinfunction "SPI-MOSI_SPI-MOSI") (pintype "passive"))
    )
    (net (code "89") (name "unconnected-(ECOG2-PadSPI-SCK)") (class "Default")
      (node (ref "ECOG2") (pin "SPI-SCK") (pinfunction "SPI-SCK_SPI-SCK") (pintype "passive"))
    )
    (net (code "90") (name "unconnected-(J1-PadLS)") (class "Default")
      (node (ref "J1") (pin "LS") (pinfunction "LS_LS") (pintype "bidirectional"))
    )
    (net (code "91") (name "unconnected-(J1-PadR)") (class "Default")
      (node (ref "J1") (pin "R") (pinfunction "R_R") (pintype "bidirectional"))
    )
    (net (code "92") (name "unconnected-(J1-PadRS)") (class "Default")
      (node (ref "J1") (pin "RS") (pinfunction "RS_RS") (pintype "bidirectional"))
    )
    (net (code "93") (name "unconnected-(S0-PadO)") (class "Default")
      (node (ref "S0") (pin "O") (pinfunction "O_O") (pintype "passive"))
    )
    (net (code "94") (name "unconnected-(S1-PadO)") (class "Default")
      (node (ref "S1") (pin "O") (pinfunction "O_O") (pintype "passive"))
    )
    (net (code "95") (name "unconnected-(S2-PadO)") (class "Default")
      (node (ref "S2") (pin "O") (pinfunction "O_O") (pintype "passive"))
    )
    (net (code "96") (name "unconnected-(S3-PadO)") (class "Default")
      (node (ref "S3") (pin "O") (pinfunction "O_O") (pintype "passive"))
    )
    (net (code "97") (name "unconnected-(S4-PadO)") (class "Default")
      (node (ref "S4") (pin "O") (pinfunction "O_O") (pintype "passive"))
    )
    (net (code "98") (name "unconnected-(S5-PadO)") (class "Default")
      (node (ref "S5") (pin "O") (pinfunction "O_O") (pintype "passive"))
    )
    (net (code "99") (name "unconnected-(S6-PadO)") (class "Default")
      (node (ref "S6") (pin "O") (pinfunction "O_O") (pintype "passive"))
    )
    (net (code "100") (name "unconnected-(S7-PadO)") (class "Default")
      (node (ref "S7") (pin "O") (pinfunction "O_O") (pintype "passive"))
    )
    (net (code "101") (name "unconnected-(X1-Pad4)") (class "Default")
      (node (ref "X1") (pin "4") (pinfunction "4_4") (pintype "passive"))
    )
    (net (code "102") (name "unconnected-(X1-Pad5)") (class "Default")
      (node (ref "X1") (pin "5") (pinfunction "5_5") (pintype "passive"))
    )
    (net (code "103") (name "unconnected-(X1-Pad9)") (class "Default")
      (node (ref "X1") (pin "9") (pinfunction "9_9") (pintype "passive"))
    )
    (net (code "104") (name "unconnected-(X1-Pad12)") (class "Default")
      (node (ref "X1") (pin "12") (pinfunction "12_12") (pintype "passive"))
    )
    (net (code "105") (name "unconnected-(X1-Pad15)") (class "Default")
      (node (ref "X1") (pin "15") (pinfunction "15_15") (pintype "passive"))
    )
  )
)
